# ecg_prototype_1.net
KiCad netlist of a schematic drawn in EAGLE
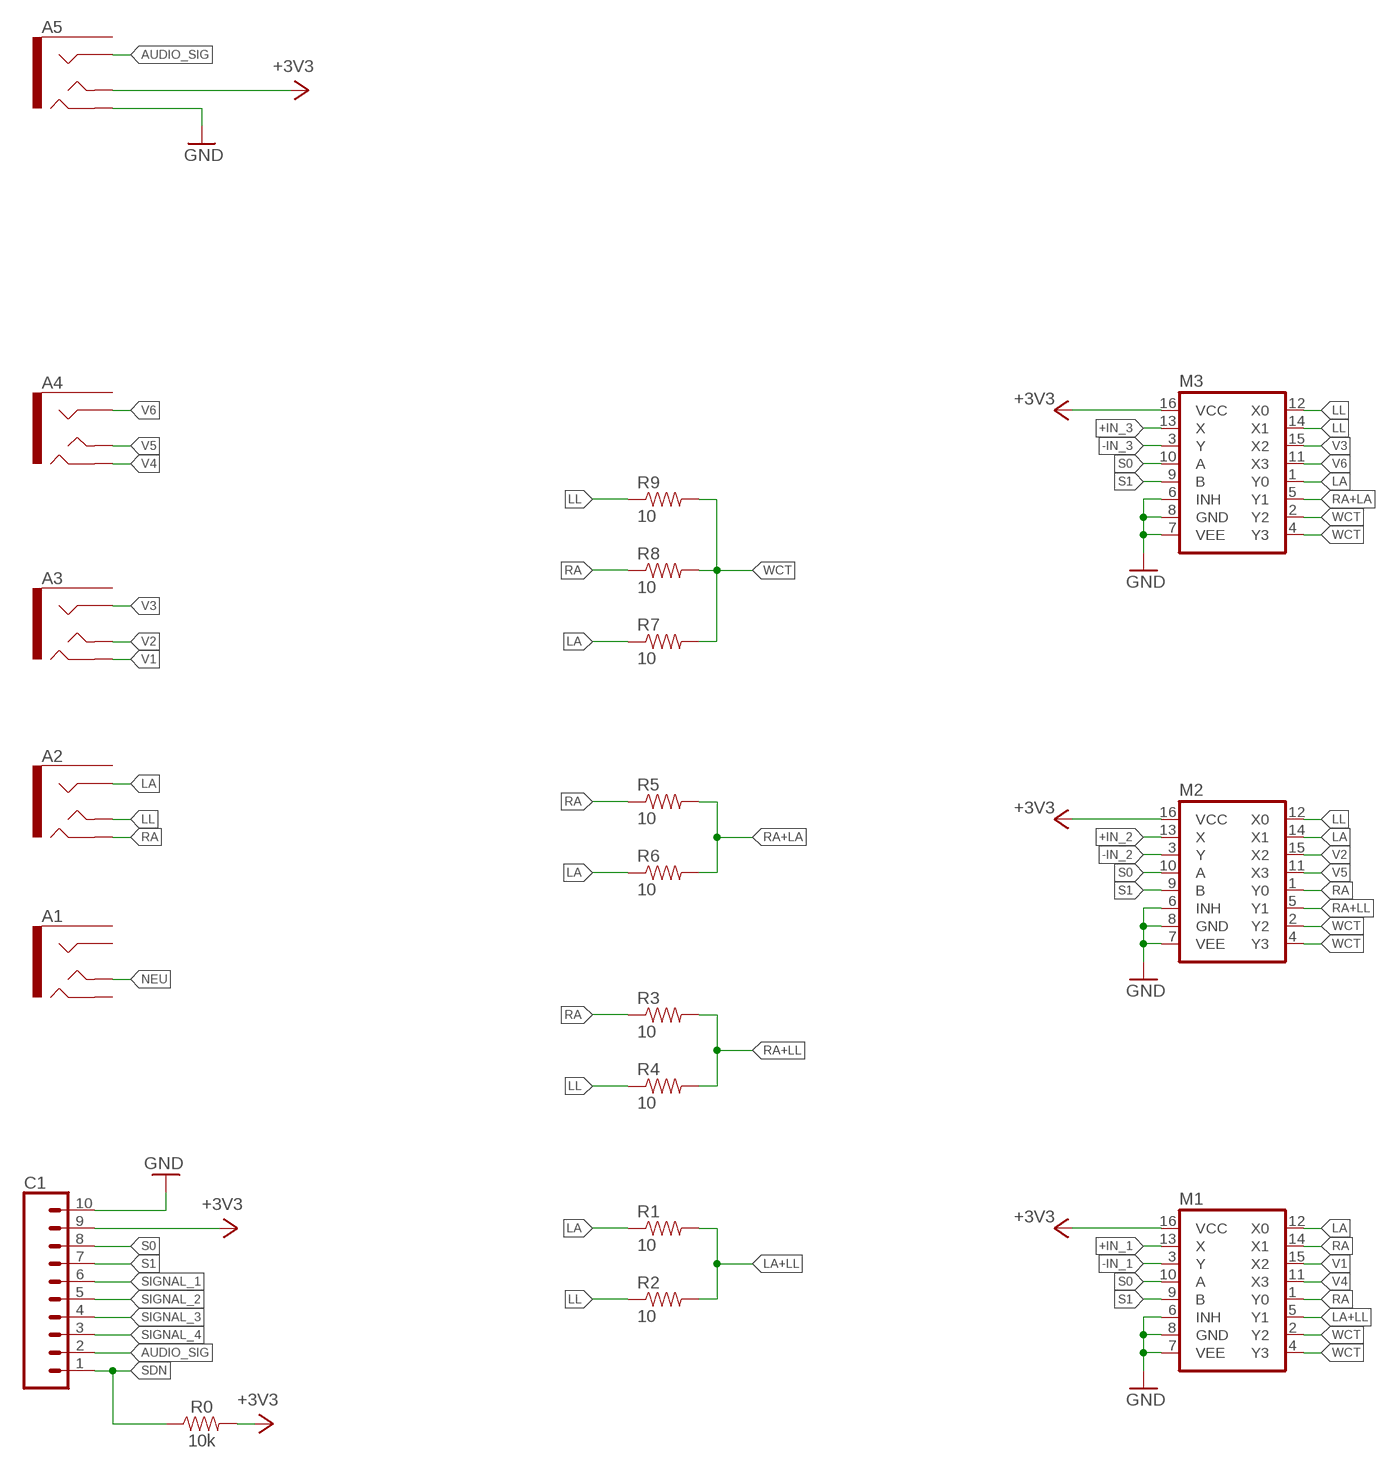
[diagram p0: schematic, sheet 1, part 1 of 2]
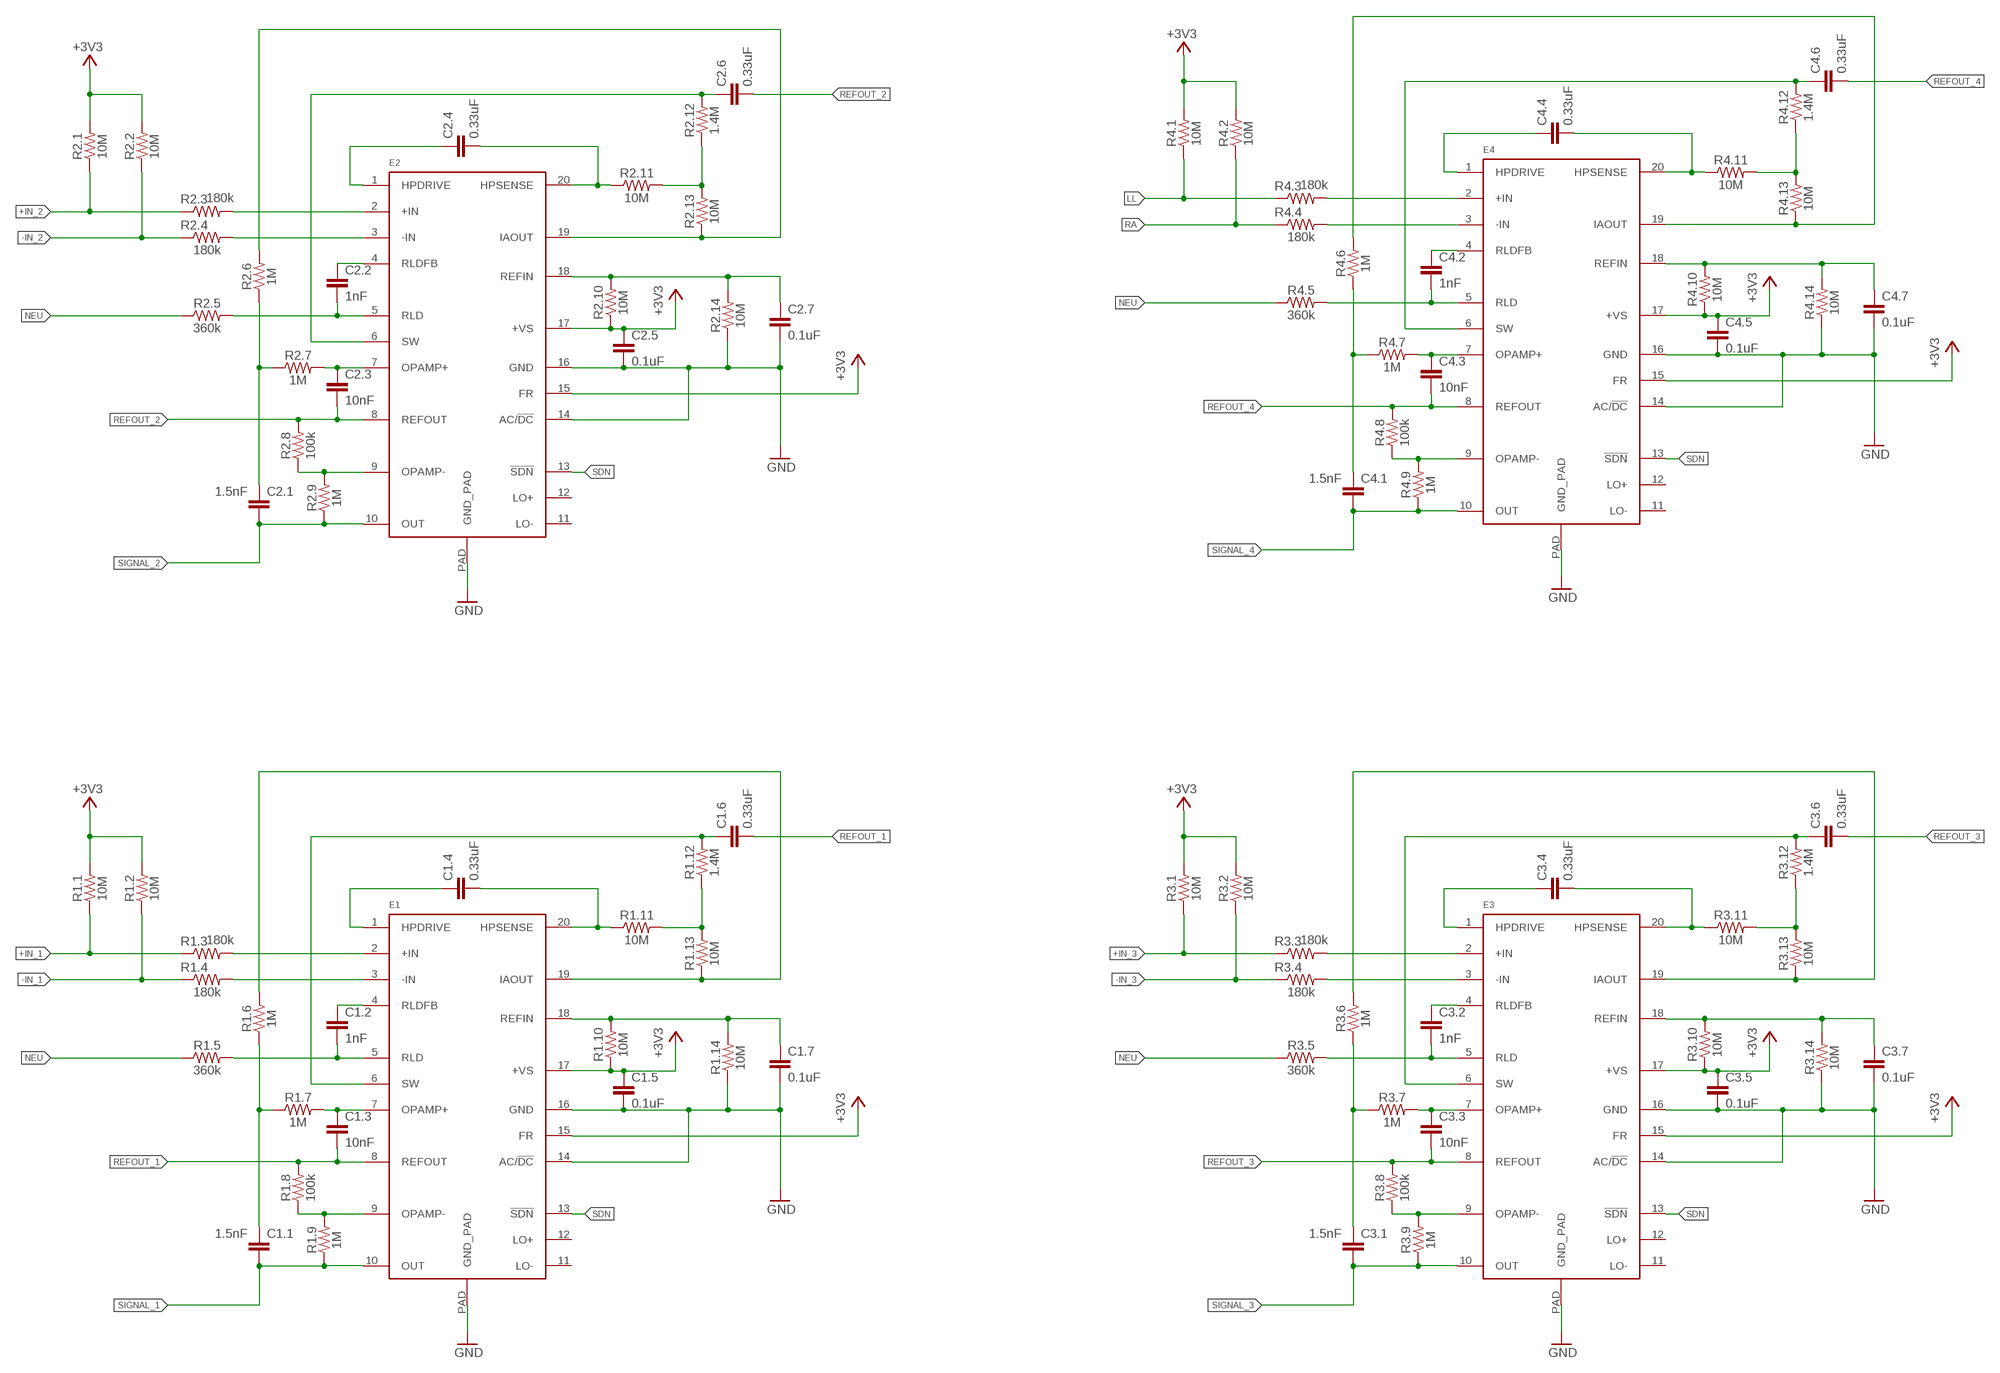
[diagram p1: schematic, sheet 1, part 2 of 2]

(export (version "E")
  (design (tool "Eeschema 10.0.6"))
  (components
    (comp (ref "A1")
      (value "AUDIO_JACK_TRRSSMD_RA")
      (footprint "eagle-import:AUDIO_JACK_3.5MM_TRRS_SMD_RA")
      (libsource (lib "eagle-import") (part "AUDIO_JACK_TRRSSMD_RA"))
    )
    (comp (ref "A2")
      (value "AUDIO_JACK_TRRSSMD_RA")
      (footprint "eagle-import:AUDIO_JACK_3.5MM_TRRS_SMD_RA")
      (libsource (lib "eagle-import") (part "AUDIO_JACK_TRRSSMD_RA"))
    )
    (comp (ref "A3")
      (value "AUDIO_JACK_TRRSSMD_RA")
      (footprint "eagle-import:AUDIO_JACK_3.5MM_TRRS_SMD_RA")
      (libsource (lib "eagle-import") (part "AUDIO_JACK_TRRSSMD_RA"))
    )
    (comp (ref "A4")
      (value "AUDIO_JACK_TRRSSMD_RA")
      (footprint "eagle-import:AUDIO_JACK_3.5MM_TRRS_SMD_RA")
      (libsource (lib "eagle-import") (part "AUDIO_JACK_TRRSSMD_RA"))
    )
    (comp (ref "A5")
      (value "AUDIO_JACK_TRRSSMD_RA")
      (footprint "eagle-import:AUDIO_JACK_3.5MM_TRRS_SMD_RA")
      (libsource (lib "eagle-import") (part "AUDIO_JACK_TRRSSMD_RA"))
    )
    (comp (ref "C1")
      (value "CONN_10\"")
      (footprint "eagle-import:1X10")
      (libsource (lib "eagle-import") (part "CONN_10{dblquote}"))
    )
    (comp (ref "C1.1")
      (value "1.5nF")
      (footprint "eagle-import:0603-CAP")
      (libsource (lib "eagle-import") (part "CAP0603-CAP"))
    )
    (comp (ref "C1.2")
      (value "1nF")
      (footprint "eagle-import:0603-CAP")
      (libsource (lib "eagle-import") (part "CAP0603-CAP"))
    )
    (comp (ref "C1.3")
      (value "10nF")
      (footprint "eagle-import:0603-CAP")
      (libsource (lib "eagle-import") (part "CAP0603-CAP"))
    )
    (comp (ref "C1.4")
      (value "0.33uF")
      (footprint "eagle-import:0805")
      (libsource (lib "eagle-import") (part "CAP0805"))
    )
    (comp (ref "C1.5")
      (value "0.1uF")
      (footprint "eagle-import:0603-CAP")
      (libsource (lib "eagle-import") (part "CAP0603-CAP"))
    )
    (comp (ref "C1.6")
      (value "0.33uF")
      (footprint "eagle-import:0805")
      (libsource (lib "eagle-import") (part "CAP0805"))
    )
    (comp (ref "C1.7")
      (value "0.1uF")
      (footprint "eagle-import:0603-CAP")
      (libsource (lib "eagle-import") (part "CAP0603-CAP"))
    )
    (comp (ref "C2.1")
      (value "1.5nF")
      (footprint "eagle-import:0603-CAP")
      (libsource (lib "eagle-import") (part "CAP0603-CAP"))
    )
    (comp (ref "C2.2")
      (value "1nF")
      (footprint "eagle-import:0603-CAP")
      (libsource (lib "eagle-import") (part "CAP0603-CAP"))
    )
    (comp (ref "C2.3")
      (value "10nF")
      (footprint "eagle-import:0603-CAP")
      (libsource (lib "eagle-import") (part "CAP0603-CAP"))
    )
    (comp (ref "C2.4")
      (value "0.33uF")
      (footprint "eagle-import:0805")
      (libsource (lib "eagle-import") (part "CAP0805"))
    )
    (comp (ref "C2.5")
      (value "0.1uF")
      (footprint "eagle-import:0603-CAP")
      (libsource (lib "eagle-import") (part "CAP0603-CAP"))
    )
    (comp (ref "C2.6")
      (value "0.33uF")
      (footprint "eagle-import:0805")
      (libsource (lib "eagle-import") (part "CAP0805"))
    )
    (comp (ref "C2.7")
      (value "0.1uF")
      (footprint "eagle-import:0603-CAP")
      (libsource (lib "eagle-import") (part "CAP0603-CAP"))
    )
    (comp (ref "C3.1")
      (value "1.5nF")
      (footprint "eagle-import:0603-CAP")
      (libsource (lib "eagle-import") (part "CAP0603-CAP"))
    )
    (comp (ref "C3.2")
      (value "1nF")
      (footprint "eagle-import:0603-CAP")
      (libsource (lib "eagle-import") (part "CAP0603-CAP"))
    )
    (comp (ref "C3.3")
      (value "10nF")
      (footprint "eagle-import:0603-CAP")
      (libsource (lib "eagle-import") (part "CAP0603-CAP"))
    )
    (comp (ref "C3.4")
      (value "0.33uF")
      (footprint "eagle-import:0805")
      (libsource (lib "eagle-import") (part "CAP0805"))
    )
    (comp (ref "C3.5")
      (value "0.1uF")
      (footprint "eagle-import:0603-CAP")
      (libsource (lib "eagle-import") (part "CAP0603-CAP"))
    )
    (comp (ref "C3.6")
      (value "0.33uF")
      (footprint "eagle-import:0805")
      (libsource (lib "eagle-import") (part "CAP0805"))
    )
    (comp (ref "C3.7")
      (value "0.1uF")
      (footprint "eagle-import:0603-CAP")
      (libsource (lib "eagle-import") (part "CAP0603-CAP"))
    )
    (comp (ref "C4.1")
      (value "1.5nF")
      (footprint "eagle-import:0603-CAP")
      (libsource (lib "eagle-import") (part "CAP0603-CAP"))
    )
    (comp (ref "C4.2")
      (value "1nF")
      (footprint "eagle-import:0603-CAP")
      (libsource (lib "eagle-import") (part "CAP0603-CAP"))
    )
    (comp (ref "C4.3")
      (value "10nF")
      (footprint "eagle-import:0603-CAP")
      (libsource (lib "eagle-import") (part "CAP0603-CAP"))
    )
    (comp (ref "C4.4")
      (value "0.33uF")
      (footprint "eagle-import:0805")
      (libsource (lib "eagle-import") (part "CAP0805"))
    )
    (comp (ref "C4.5")
      (value "0.1uF")
      (footprint "eagle-import:0603-CAP")
      (libsource (lib "eagle-import") (part "CAP0603-CAP"))
    )
    (comp (ref "C4.6")
      (value "0.33uF")
      (footprint "eagle-import:0805")
      (libsource (lib "eagle-import") (part "CAP0805"))
    )
    (comp (ref "C4.7")
      (value "0.1uF")
      (footprint "eagle-import:0603-CAP")
      (libsource (lib "eagle-import") (part "CAP0603-CAP"))
    )
    (comp (ref "E1")
      (value "AD8232ACPZ-R7")
      (footprint "eagle-import:LFCSP_20")
      (libsource (lib "eagle-import") (part "AD8232"))
    )
    (comp (ref "E2")
      (value "AD8232ACPZ-R7")
      (footprint "eagle-import:LFCSP_20")
      (libsource (lib "eagle-import") (part "AD8232"))
    )
    (comp (ref "E3")
      (value "AD8232ACPZ-R7")
      (footprint "eagle-import:LFCSP_20")
      (libsource (lib "eagle-import") (part "AD8232"))
    )
    (comp (ref "E4")
      (value "AD8232ACPZ-R7")
      (footprint "eagle-import:LFCSP_20")
      (libsource (lib "eagle-import") (part "AD8232"))
    )
    (comp (ref "M1")
      (value "74HC4052D")
      (footprint "eagle-import:SO16")
      (libsource (lib "eagle-import") (part "744052DHC"))
    )
    (comp (ref "M2")
      (value "74HC4052D")
      (footprint "eagle-import:SO16")
      (libsource (lib "eagle-import") (part "744052DHC"))
    )
    (comp (ref "M3")
      (value "74HC4052D")
      (footprint "eagle-import:SO16")
      (libsource (lib "eagle-import") (part "744052DHC"))
    )
    (comp (ref "R0")
      (value "10k")
      (footprint "eagle-import:0603")
      (libsource (lib "eagle-import") (part "10KOHM-0603-1/10W-1%"))
    )
    (comp (ref "R1")
      (value "10")
      (footprint "eagle-import:0402-RES")
      (libsource (lib "eagle-import") (part "RESISTOR0402-RES"))
    )
    (comp (ref "R1.1")
      (value "10M")
      (footprint "eagle-import:0603")
      (libsource (lib "eagle-import") (part "RESISTOR0603"))
    )
    (comp (ref "R1.2")
      (value "10M")
      (footprint "eagle-import:0603")
      (libsource (lib "eagle-import") (part "RESISTOR0603"))
    )
    (comp (ref "R1.3")
      (value "180k")
      (footprint "eagle-import:0603")
      (libsource (lib "eagle-import") (part "RESISTOR0603"))
    )
    (comp (ref "R1.4")
      (value "180k")
      (footprint "eagle-import:0603")
      (libsource (lib "eagle-import") (part "RESISTOR0603"))
    )
    (comp (ref "R1.5")
      (value "360k")
      (footprint "eagle-import:0603")
      (libsource (lib "eagle-import") (part "RESISTOR0603"))
    )
    (comp (ref "R1.6")
      (value "1M")
      (footprint "eagle-import:0603")
      (libsource (lib "eagle-import") (part "RESISTOR0603"))
    )
    (comp (ref "R1.7")
      (value "1M")
      (footprint "eagle-import:0603")
      (libsource (lib "eagle-import") (part "RESISTOR0603"))
    )
    (comp (ref "R1.8")
      (value "100k")
      (footprint "eagle-import:0603")
      (libsource (lib "eagle-import") (part "RESISTOR0603"))
    )
    (comp (ref "R1.9")
      (value "1M")
      (footprint "eagle-import:0603")
      (libsource (lib "eagle-import") (part "RESISTOR0603"))
    )
    (comp (ref "R1.10")
      (value "10M")
      (footprint "eagle-import:0603")
      (libsource (lib "eagle-import") (part "RESISTOR0603"))
    )
    (comp (ref "R1.11")
      (value "10M")
      (footprint "eagle-import:0603")
      (libsource (lib "eagle-import") (part "RESISTOR0603"))
    )
    (comp (ref "R1.12")
      (value "1.4M")
      (footprint "eagle-import:0603")
      (libsource (lib "eagle-import") (part "RESISTOR0603"))
    )
    (comp (ref "R1.13")
      (value "10M")
      (footprint "eagle-import:0603")
      (libsource (lib "eagle-import") (part "RESISTOR0603"))
    )
    (comp (ref "R1.14")
      (value "10M")
      (footprint "eagle-import:0603")
      (libsource (lib "eagle-import") (part "RESISTOR0603"))
    )
    (comp (ref "R2")
      (value "10")
      (footprint "eagle-import:0402-RES")
      (libsource (lib "eagle-import") (part "RESISTOR0402-RES"))
    )
    (comp (ref "R2.1")
      (value "10M")
      (footprint "eagle-import:0603")
      (libsource (lib "eagle-import") (part "RESISTOR0603"))
    )
    (comp (ref "R2.2")
      (value "10M")
      (footprint "eagle-import:0603")
      (libsource (lib "eagle-import") (part "RESISTOR0603"))
    )
    (comp (ref "R2.3")
      (value "180k")
      (footprint "eagle-import:0603")
      (libsource (lib "eagle-import") (part "RESISTOR0603"))
    )
    (comp (ref "R2.4")
      (value "180k")
      (footprint "eagle-import:0603")
      (libsource (lib "eagle-import") (part "RESISTOR0603"))
    )
    (comp (ref "R2.5")
      (value "360k")
      (footprint "eagle-import:0603")
      (libsource (lib "eagle-import") (part "RESISTOR0603"))
    )
    (comp (ref "R2.6")
      (value "1M")
      (footprint "eagle-import:0603")
      (libsource (lib "eagle-import") (part "RESISTOR0603"))
    )
    (comp (ref "R2.7")
      (value "1M")
      (footprint "eagle-import:0603")
      (libsource (lib "eagle-import") (part "RESISTOR0603"))
    )
    (comp (ref "R2.8")
      (value "100k")
      (footprint "eagle-import:0603")
      (libsource (lib "eagle-import") (part "RESISTOR0603"))
    )
    (comp (ref "R2.9")
      (value "1M")
      (footprint "eagle-import:0603")
      (libsource (lib "eagle-import") (part "RESISTOR0603"))
    )
    (comp (ref "R2.10")
      (value "10M")
      (footprint "eagle-import:0603")
      (libsource (lib "eagle-import") (part "RESISTOR0603"))
    )
    (comp (ref "R2.11")
      (value "10M")
      (footprint "eagle-import:0603")
      (libsource (lib "eagle-import") (part "RESISTOR0603"))
    )
    (comp (ref "R2.12")
      (value "1.4M")
      (footprint "eagle-import:0603")
      (libsource (lib "eagle-import") (part "RESISTOR0603"))
    )
    (comp (ref "R2.13")
      (value "10M")
      (footprint "eagle-import:0603")
      (libsource (lib "eagle-import") (part "RESISTOR0603"))
    )
    (comp (ref "R2.14")
      (value "10M")
      (footprint "eagle-import:0603")
      (libsource (lib "eagle-import") (part "RESISTOR0603"))
    )
    (comp (ref "R3")
      (value "10")
      (footprint "eagle-import:0402-RES")
      (libsource (lib "eagle-import") (part "RESISTOR0402-RES"))
    )
    (comp (ref "R3.1")
      (value "10M")
      (footprint "eagle-import:0603")
      (libsource (lib "eagle-import") (part "RESISTOR0603"))
    )
    (comp (ref "R3.2")
      (value "10M")
      (footprint "eagle-import:0603")
      (libsource (lib "eagle-import") (part "RESISTOR0603"))
    )
    (comp (ref "R3.3")
      (value "180k")
      (footprint "eagle-import:0603")
      (libsource (lib "eagle-import") (part "RESISTOR0603"))
    )
    (comp (ref "R3.4")
      (value "180k")
      (footprint "eagle-import:0603")
      (libsource (lib "eagle-import") (part "RESISTOR0603"))
    )
    (comp (ref "R3.5")
      (value "360k")
      (footprint "eagle-import:0603")
      (libsource (lib "eagle-import") (part "RESISTOR0603"))
    )
    (comp (ref "R3.6")
      (value "1M")
      (footprint "eagle-import:0603")
      (libsource (lib "eagle-import") (part "RESISTOR0603"))
    )
    (comp (ref "R3.7")
      (value "1M")
      (footprint "eagle-import:0603")
      (libsource (lib "eagle-import") (part "RESISTOR0603"))
    )
    (comp (ref "R3.8")
      (value "100k")
      (footprint "eagle-import:0603")
      (libsource (lib "eagle-import") (part "RESISTOR0603"))
    )
    (comp (ref "R3.9")
      (value "1M")
      (footprint "eagle-import:0603")
      (libsource (lib "eagle-import") (part "RESISTOR0603"))
    )
    (comp (ref "R3.10")
      (value "10M")
      (footprint "eagle-import:0603")
      (libsource (lib "eagle-import") (part "RESISTOR0603"))
    )
    (comp (ref "R3.11")
      (value "10M")
      (footprint "eagle-import:0603")
      (libsource (lib "eagle-import") (part "RESISTOR0603"))
    )
    (comp (ref "R3.12")
      (value "1.4M")
      (footprint "eagle-import:0603")
      (libsource (lib "eagle-import") (part "RESISTOR0603"))
    )
    (comp (ref "R3.13")
      (value "10M")
      (footprint "eagle-import:0603")
      (libsource (lib "eagle-import") (part "RESISTOR0603"))
    )
    (comp (ref "R3.14")
      (value "10M")
      (footprint "eagle-import:0603")
      (libsource (lib "eagle-import") (part "RESISTOR0603"))
    )
    (comp (ref "R4")
      (value "10")
      (footprint "eagle-import:0402-RES")
      (libsource (lib "eagle-import") (part "RESISTOR0402-RES"))
    )
    (comp (ref "R4.1")
      (value "10M")
      (footprint "eagle-import:0603")
      (libsource (lib "eagle-import") (part "RESISTOR0603"))
    )
    (comp (ref "R4.2")
      (value "10M")
      (footprint "eagle-import:0603")
      (libsource (lib "eagle-import") (part "RESISTOR0603"))
    )
    (comp (ref "R4.3")
      (value "180k")
      (footprint "eagle-import:0603")
      (libsource (lib "eagle-import") (part "RESISTOR0603"))
    )
    (comp (ref "R4.4")
      (value "180k")
      (footprint "eagle-import:0603")
      (libsource (lib "eagle-import") (part "RESISTOR0603"))
    )
    (comp (ref "R4.5")
      (value "360k")
      (footprint "eagle-import:0603")
      (libsource (lib "eagle-import") (part "RESISTOR0603"))
    )
    (comp (ref "R4.6")
      (value "1M")
      (footprint "eagle-import:0603")
      (libsource (lib "eagle-import") (part "RESISTOR0603"))
    )
    (comp (ref "R4.7")
      (value "1M")
      (footprint "eagle-import:0603")
      (libsource (lib "eagle-import") (part "RESISTOR0603"))
    )
    (comp (ref "R4.8")
      (value "100k")
      (footprint "eagle-import:0603")
      (libsource (lib "eagle-import") (part "RESISTOR0603"))
    )
    (comp (ref "R4.9")
      (value "1M")
      (footprint "eagle-import:0603")
      (libsource (lib "eagle-import") (part "RESISTOR0603"))
    )
    (comp (ref "R4.10")
      (value "10M")
      (footprint "eagle-import:0603")
      (libsource (lib "eagle-import") (part "RESISTOR0603"))
    )
    (comp (ref "R4.11")
      (value "10M")
      (footprint "eagle-import:0603")
      (libsource (lib "eagle-import") (part "RESISTOR0603"))
    )
    (comp (ref "R4.12")
      (value "1.4M")
      (footprint "eagle-import:0603")
      (libsource (lib "eagle-import") (part "RESISTOR0603"))
    )
    (comp (ref "R4.13")
      (value "10M")
      (footprint "eagle-import:0603")
      (libsource (lib "eagle-import") (part "RESISTOR0603"))
    )
    (comp (ref "R4.14")
      (value "10M")
      (footprint "eagle-import:0603")
      (libsource (lib "eagle-import") (part "RESISTOR0603"))
    )
    (comp (ref "R5")
      (value "10")
      (footprint "eagle-import:0402-RES")
      (libsource (lib "eagle-import") (part "RESISTOR0402-RES"))
    )
    (comp (ref "R6")
      (value "10")
      (footprint "eagle-import:0402-RES")
      (libsource (lib "eagle-import") (part "RESISTOR0402-RES"))
    )
    (comp (ref "R7")
      (value "10")
      (footprint "eagle-import:0402-RES")
      (libsource (lib "eagle-import") (part "RESISTOR0402-RES"))
    )
    (comp (ref "R8")
      (value "10")
      (footprint "eagle-import:0402-RES")
      (libsource (lib "eagle-import") (part "RESISTOR0402-RES"))
    )
    (comp (ref "R9")
      (value "10")
      (footprint "eagle-import:0402-RES")
      (libsource (lib "eagle-import") (part "RESISTOR0402-RES"))
    )
  )
  (nets
    (net (code "1") (name "+3V3") (class "Default")
      (node (ref "A5") (pin "TIP") (pinfunction "TIP_TIP") (pintype "bidirectional"))
      (node (ref "C1") (pin "9") (pinfunction "9_9") (pintype "passive"))
      (node (ref "C1.5") (pin "1") (pinfunction "1_1") (pintype "passive"))
      (node (ref "C2.5") (pin "1") (pinfunction "1_1") (pintype "passive"))
      (node (ref "C3.5") (pin "1") (pinfunction "1_1") (pintype "passive"))
      (node (ref "C4.5") (pin "1") (pinfunction "1_1") (pintype "passive"))
      (node (ref "E1") (pin "15") (pinfunction "FR_15") (pintype "bidirectional"))
      (node (ref "E1") (pin "17") (pinfunction "+VS_17") (pintype "bidirectional"))
      (node (ref "E2") (pin "15") (pinfunction "FR_15") (pintype "bidirectional"))
      (node (ref "E2") (pin "17") (pinfunction "+VS_17") (pintype "bidirectional"))
      (node (ref "E3") (pin "15") (pinfunction "FR_15") (pintype "bidirectional"))
      (node (ref "E3") (pin "17") (pinfunction "+VS_17") (pintype "bidirectional"))
      (node (ref "E4") (pin "15") (pinfunction "FR_15") (pintype "bidirectional"))
      (node (ref "E4") (pin "17") (pinfunction "+VS_17") (pintype "bidirectional"))
      (node (ref "M1") (pin "16") (pinfunction "VCC_16") (pintype "power_in"))
      (node (ref "M2") (pin "16") (pinfunction "VCC_16") (pintype "power_in"))
      (node (ref "M3") (pin "16") (pinfunction "VCC_16") (pintype "power_in"))
      (node (ref "R0") (pin "2") (pinfunction "2_2") (pintype "passive"))
      (node (ref "R1.1") (pin "2") (pinfunction "2_2") (pintype "passive"))
      (node (ref "R1.10") (pin "1") (pinfunction "1_1") (pintype "passive"))
      (node (ref "R1.2") (pin "2") (pinfunction "2_2") (pintype "passive"))
      (node (ref "R2.1") (pin "2") (pinfunction "2_2") (pintype "passive"))
      (node (ref "R2.10") (pin "1") (pinfunction "1_1") (pintype "passive"))
      (node (ref "R2.2") (pin "2") (pinfunction "2_2") (pintype "passive"))
      (node (ref "R3.1") (pin "2") (pinfunction "2_2") (pintype "passive"))
      (node (ref "R3.10") (pin "1") (pinfunction "1_1") (pintype "passive"))
      (node (ref "R3.2") (pin "2") (pinfunction "2_2") (pintype "passive"))
      (node (ref "R4.1") (pin "2") (pinfunction "2_2") (pintype "passive"))
      (node (ref "R4.10") (pin "1") (pinfunction "1_1") (pintype "passive"))
      (node (ref "R4.2") (pin "2") (pinfunction "2_2") (pintype "passive"))
    )
    (net (code "2") (name "+IN_1") (class "Default")
      (node (ref "M1") (pin "13") (pinfunction "X_13") (pintype "bidirectional"))
      (node (ref "R1.1") (pin "1") (pinfunction "1_1") (pintype "passive"))
      (node (ref "R1.3") (pin "1") (pinfunction "1_1") (pintype "passive"))
    )
    (net (code "3") (name "+IN_2") (class "Default")
      (node (ref "M2") (pin "13") (pinfunction "X_13") (pintype "bidirectional"))
      (node (ref "R2.1") (pin "1") (pinfunction "1_1") (pintype "passive"))
      (node (ref "R2.3") (pin "1") (pinfunction "1_1") (pintype "passive"))
    )
    (net (code "4") (name "+IN_3") (class "Default")
      (node (ref "M3") (pin "13") (pinfunction "X_13") (pintype "bidirectional"))
      (node (ref "R3.1") (pin "1") (pinfunction "1_1") (pintype "passive"))
      (node (ref "R3.3") (pin "1") (pinfunction "1_1") (pintype "passive"))
    )
    (net (code "5") (name "-IN_1") (class "Default")
      (node (ref "M1") (pin "3") (pinfunction "Y_3") (pintype "bidirectional"))
      (node (ref "R1.2") (pin "1") (pinfunction "1_1") (pintype "passive"))
      (node (ref "R1.4") (pin "1") (pinfunction "1_1") (pintype "passive"))
    )
    (net (code "6") (name "-IN_2") (class "Default")
      (node (ref "M2") (pin "3") (pinfunction "Y_3") (pintype "bidirectional"))
      (node (ref "R2.2") (pin "1") (pinfunction "1_1") (pintype "passive"))
      (node (ref "R2.4") (pin "1") (pinfunction "1_1") (pintype "passive"))
    )
    (net (code "7") (name "-IN_3") (class "Default")
      (node (ref "M3") (pin "3") (pinfunction "Y_3") (pintype "bidirectional"))
      (node (ref "R3.2") (pin "1") (pinfunction "1_1") (pintype "passive"))
      (node (ref "R3.4") (pin "1") (pinfunction "1_1") (pintype "passive"))
    )
    (net (code "8") (name "AUDIO_SIG") (class "Default")
      (node (ref "A5") (pin "RING1") (pinfunction "RING1_RING1") (pintype "bidirectional"))
      (node (ref "C1") (pin "2") (pinfunction "2_2") (pintype "passive"))
    )
    (net (code "9") (name "GND") (class "Default")
      (node (ref "A5") (pin "RING2") (pinfunction "RING2_RING2") (pintype "bidirectional"))
      (node (ref "C1") (pin "10") (pinfunction "10_10") (pintype "passive"))
      (node (ref "C1.5") (pin "2") (pinfunction "2_2") (pintype "passive"))
      (node (ref "C1.7") (pin "2") (pinfunction "2_2") (pintype "passive"))
      (node (ref "C2.5") (pin "2") (pinfunction "2_2") (pintype "passive"))
      (node (ref "C2.7") (pin "2") (pinfunction "2_2") (pintype "passive"))
      (node (ref "C3.5") (pin "2") (pinfunction "2_2") (pintype "passive"))
      (node (ref "C3.7") (pin "2") (pinfunction "2_2") (pintype "passive"))
      (node (ref "C4.5") (pin "2") (pinfunction "2_2") (pintype "passive"))
      (node (ref "C4.7") (pin "2") (pinfunction "2_2") (pintype "passive"))
      (node (ref "E1") (pin "14") (pinfunction "AC/~{DC}_14") (pintype "bidirectional"))
      (node (ref "E1") (pin "16") (pinfunction "GND_16") (pintype "bidirectional"))
      (node (ref "E1") (pin "PAD") (pinfunction "GND_PAD_PAD") (pintype "bidirectional"))
      (node (ref "E2") (pin "14") (pinfunction "AC/~{DC}_14") (pintype "bidirectional"))
      (node (ref "E2") (pin "16") (pinfunction "GND_16") (pintype "bidirectional"))
      (node (ref "E2") (pin "PAD") (pinfunction "GND_PAD_PAD") (pintype "bidirectional"))
      (node (ref "E3") (pin "14") (pinfunction "AC/~{DC}_14") (pintype "bidirectional"))
      (node (ref "E3") (pin "16") (pinfunction "GND_16") (pintype "bidirectional"))
      (node (ref "E3") (pin "PAD") (pinfunction "GND_PAD_PAD") (pintype "bidirectional"))
      (node (ref "E4") (pin "14") (pinfunction "AC/~{DC}_14") (pintype "bidirectional"))
      (node (ref "E4") (pin "16") (pinfunction "GND_16") (pintype "bidirectional"))
      (node (ref "E4") (pin "PAD") (pinfunction "GND_PAD_PAD") (pintype "bidirectional"))
      (node (ref "M1") (pin "6") (pinfunction "INH_6") (pintype "input"))
      (node (ref "M1") (pin "7") (pinfunction "VEE_7") (pintype "power_in"))
      (node (ref "M1") (pin "8") (pinfunction "GND_8") (pintype "power_in"))
      (node (ref "M2") (pin "6") (pinfunction "INH_6") (pintype "input"))
      (node (ref "M2") (pin "7") (pinfunction "VEE_7") (pintype "power_in"))
      (node (ref "M2") (pin "8") (pinfunction "GND_8") (pintype "power_in"))
      (node (ref "M3") (pin "6") (pinfunction "INH_6") (pintype "input"))
      (node (ref "M3") (pin "7") (pinfunction "VEE_7") (pintype "power_in"))
      (node (ref "M3") (pin "8") (pinfunction "GND_8") (pintype "power_in"))
      (node (ref "R1.14") (pin "1") (pinfunction "1_1") (pintype "passive"))
      (node (ref "R2.14") (pin "1") (pinfunction "1_1") (pintype "passive"))
      (node (ref "R3.14") (pin "1") (pinfunction "1_1") (pintype "passive"))
      (node (ref "R4.14") (pin "1") (pinfunction "1_1") (pintype "passive"))
    )
    (net (code "10") (name "LA") (class "Default")
      (node (ref "A2") (pin "RING1") (pinfunction "RING1_RING1") (pintype "bidirectional"))
      (node (ref "M1") (pin "12") (pinfunction "X0_12") (pintype "bidirectional"))
      (node (ref "M2") (pin "14") (pinfunction "X1_14") (pintype "bidirectional"))
      (node (ref "M3") (pin "1") (pinfunction "Y0_1") (pintype "bidirectional"))
      (node (ref "R1") (pin "1") (pinfunction "1_1") (pintype "passive"))
      (node (ref "R6") (pin "1") (pinfunction "1_1") (pintype "passive"))
      (node (ref "R7") (pin "1") (pinfunction "1_1") (pintype "passive"))
    )
    (net (code "11") (name "LA+LL") (class "Default")
      (node (ref "M1") (pin "5") (pinfunction "Y1_5") (pintype "bidirectional"))
      (node (ref "R1") (pin "2") (pinfunction "2_2") (pintype "passive"))
      (node (ref "R2") (pin "2") (pinfunction "2_2") (pintype "passive"))
    )
    (net (code "12") (name "LL") (class "Default")
      (node (ref "A2") (pin "TIP") (pinfunction "TIP_TIP") (pintype "bidirectional"))
      (node (ref "M2") (pin "12") (pinfunction "X0_12") (pintype "bidirectional"))
      (node (ref "M3") (pin "12") (pinfunction "X0_12") (pintype "bidirectional"))
      (node (ref "M3") (pin "14") (pinfunction "X1_14") (pintype "bidirectional"))
      (node (ref "R2") (pin "1") (pinfunction "1_1") (pintype "passive"))
      (node (ref "R4") (pin "1") (pinfunction "1_1") (pintype "passive"))
      (node (ref "R4.1") (pin "1") (pinfunction "1_1") (pintype "passive"))
      (node (ref "R4.3") (pin "1") (pinfunction "1_1") (pintype "passive"))
      (node (ref "R9") (pin "1") (pinfunction "1_1") (pintype "passive"))
    )
    (net (code "13") (name "NEU") (class "Default")
      (node (ref "A1") (pin "TIP") (pinfunction "TIP_TIP") (pintype "bidirectional"))
      (node (ref "R1.5") (pin "1") (pinfunction "1_1") (pintype "passive"))
      (node (ref "R2.5") (pin "1") (pinfunction "1_1") (pintype "passive"))
      (node (ref "R3.5") (pin "1") (pinfunction "1_1") (pintype "passive"))
      (node (ref "R4.5") (pin "1") (pinfunction "1_1") (pintype "passive"))
    )
    (net (code "14") (name "Net-(C1.1-Pad1)") (class "Default")
      (node (ref "C1.1") (pin "1") (pinfunction "1_1") (pintype "passive"))
      (node (ref "R1.6") (pin "1") (pinfunction "1_1") (pintype "passive"))
      (node (ref "R1.7") (pin "1") (pinfunction "1_1") (pintype "passive"))
    )
    (net (code "15") (name "Net-(C2.1-Pad1)") (class "Default")
      (node (ref "C2.1") (pin "1") (pinfunction "1_1") (pintype "passive"))
      (node (ref "R2.6") (pin "1") (pinfunction "1_1") (pintype "passive"))
      (node (ref "R2.7") (pin "1") (pinfunction "1_1") (pintype "passive"))
    )
    (net (code "16") (name "Net-(C3.1-Pad1)") (class "Default")
      (node (ref "C3.1") (pin "1") (pinfunction "1_1") (pintype "passive"))
      (node (ref "R3.6") (pin "1") (pinfunction "1_1") (pintype "passive"))
      (node (ref "R3.7") (pin "1") (pinfunction "1_1") (pintype "passive"))
    )
    (net (code "17") (name "Net-(C4.1-Pad1)") (class "Default")
      (node (ref "C4.1") (pin "1") (pinfunction "1_1") (pintype "passive"))
      (node (ref "R4.6") (pin "1") (pinfunction "1_1") (pintype "passive"))
      (node (ref "R4.7") (pin "1") (pinfunction "1_1") (pintype "passive"))
    )
    (net (code "18") (name "Net-(E1-+IN)") (class "Default")
      (node (ref "E1") (pin "2") (pinfunction "+IN_2") (pintype "bidirectional"))
      (node (ref "R1.3") (pin "2") (pinfunction "2_2") (pintype "passive"))
    )
    (net (code "19") (name "Net-(E1--IN)") (class "Default")
      (node (ref "E1") (pin "3") (pinfunction "-IN_3") (pintype "bidirectional"))
      (node (ref "R1.4") (pin "2") (pinfunction "2_2") (pintype "passive"))
    )
    (net (code "20") (name "Net-(E1-HPDRIVE)") (class "Default")
      (node (ref "C1.4") (pin "1") (pinfunction "1_1") (pintype "passive"))
      (node (ref "E1") (pin "1") (pinfunction "HPDRIVE_1") (pintype "bidirectional"))
    )
    (net (code "21") (name "Net-(E1-HPSENSE)") (class "Default")
      (node (ref "C1.4") (pin "2") (pinfunction "2_2") (pintype "passive"))
      (node (ref "E1") (pin "20") (pinfunction "HPSENSE_20") (pintype "bidirectional"))
      (node (ref "R1.11") (pin "1") (pinfunction "1_1") (pintype "passive"))
    )
    (net (code "22") (name "Net-(E1-IAOUT)") (class "Default")
      (node (ref "E1") (pin "19") (pinfunction "IAOUT_19") (pintype "bidirectional"))
      (node (ref "R1.13") (pin "1") (pinfunction "1_1") (pintype "passive"))
      (node (ref "R1.6") (pin "2") (pinfunction "2_2") (pintype "passive"))
    )
    (net (code "23") (name "Net-(E1-OPAMP+)") (class "Default")
      (node (ref "C1.3") (pin "1") (pinfunction "1_1") (pintype "passive"))
      (node (ref "E1") (pin "7") (pinfunction "OPAMP+_7") (pintype "bidirectional"))
      (node (ref "R1.7") (pin "2") (pinfunction "2_2") (pintype "passive"))
    )
    (net (code "24") (name "Net-(E1-OPAMP-)") (class "Default")
      (node (ref "E1") (pin "9") (pinfunction "OPAMP-_9") (pintype "bidirectional"))
      (node (ref "R1.8") (pin "1") (pinfunction "1_1") (pintype "passive"))
      (node (ref "R1.9") (pin "2") (pinfunction "2_2") (pintype "passive"))
    )
    (net (code "25") (name "Net-(E1-REFIN)") (class "Default")
      (node (ref "C1.7") (pin "1") (pinfunction "1_1") (pintype "passive"))
      (node (ref "E1") (pin "18") (pinfunction "REFIN_18") (pintype "bidirectional"))
      (node (ref "R1.10") (pin "2") (pinfunction "2_2") (pintype "passive"))
      (node (ref "R1.14") (pin "2") (pinfunction "2_2") (pintype "passive"))
    )
    (net (code "26") (name "Net-(E1-RLD)") (class "Default")
      (node (ref "C1.2") (pin "2") (pinfunction "2_2") (pintype "passive"))
      (node (ref "E1") (pin "5") (pinfunction "RLD_5") (pintype "bidirectional"))
      (node (ref "R1.5") (pin "2") (pinfunction "2_2") (pintype "passive"))
    )
    (net (code "27") (name "Net-(E1-RLDFB)") (class "Default")
      (node (ref "C1.2") (pin "1") (pinfunction "1_1") (pintype "passive"))
      (node (ref "E1") (pin "4") (pinfunction "RLDFB_4") (pintype "bidirectional"))
    )
    (net (code "28") (name "Net-(E1-SW)") (class "Default")
      (node (ref "C1.6") (pin "1") (pinfunction "1_1") (pintype "passive"))
      (node (ref "E1") (pin "6") (pinfunction "SW_6") (pintype "bidirectional"))
      (node (ref "R1.12") (pin "2") (pinfunction "2_2") (pintype "passive"))
    )
    (net (code "29") (name "Net-(E2-+IN)") (class "Default")
      (node (ref "E2") (pin "2") (pinfunction "+IN_2") (pintype "bidirectional"))
      (node (ref "R2.3") (pin "2") (pinfunction "2_2") (pintype "passive"))
    )
    (net (code "30") (name "Net-(E2--IN)") (class "Default")
      (node (ref "E2") (pin "3") (pinfunction "-IN_3") (pintype "bidirectional"))
      (node (ref "R2.4") (pin "2") (pinfunction "2_2") (pintype "passive"))
    )
    (net (code "31") (name "Net-(E2-HPDRIVE)") (class "Default")
      (node (ref "C2.4") (pin "1") (pinfunction "1_1") (pintype "passive"))
      (node (ref "E2") (pin "1") (pinfunction "HPDRIVE_1") (pintype "bidirectional"))
    )
    (net (code "32") (name "Net-(E2-HPSENSE)") (class "Default")
      (node (ref "C2.4") (pin "2") (pinfunction "2_2") (pintype "passive"))
      (node (ref "E2") (pin "20") (pinfunction "HPSENSE_20") (pintype "bidirectional"))
      (node (ref "R2.11") (pin "1") (pinfunction "1_1") (pintype "passive"))
    )
    (net (code "33") (name "Net-(E2-IAOUT)") (class "Default")
      (node (ref "E2") (pin "19") (pinfunction "IAOUT_19") (pintype "bidirectional"))
      (node (ref "R2.13") (pin "1") (pinfunction "1_1") (pintype "passive"))
      (node (ref "R2.6") (pin "2") (pinfunction "2_2") (pintype "passive"))
    )
    (net (code "34") (name "Net-(E2-OPAMP+)") (class "Default")
      (node (ref "C2.3") (pin "1") (pinfunction "1_1") (pintype "passive"))
      (node (ref "E2") (pin "7") (pinfunction "OPAMP+_7") (pintype "bidirectional"))
      (node (ref "R2.7") (pin "2") (pinfunction "2_2") (pintype "passive"))
    )
    (net (code "35") (name "Net-(E2-OPAMP-)") (class "Default")
      (node (ref "E2") (pin "9") (pinfunction "OPAMP-_9") (pintype "bidirectional"))
      (node (ref "R2.8") (pin "1") (pinfunction "1_1") (pintype "passive"))
      (node (ref "R2.9") (pin "2") (pinfunction "2_2") (pintype "passive"))
    )
    (net (code "36") (name "Net-(E2-REFIN)") (class "Default")
      (node (ref "C2.7") (pin "1") (pinfunction "1_1") (pintype "passive"))
      (node (ref "E2") (pin "18") (pinfunction "REFIN_18") (pintype "bidirectional"))
      (node (ref "R2.10") (pin "2") (pinfunction "2_2") (pintype "passive"))
      (node (ref "R2.14") (pin "2") (pinfunction "2_2") (pintype "passive"))
    )
    (net (code "37") (name "Net-(E2-RLD)") (class "Default")
      (node (ref "C2.2") (pin "2") (pinfunction "2_2") (pintype "passive"))
      (node (ref "E2") (pin "5") (pinfunction "RLD_5") (pintype "bidirectional"))
      (node (ref "R2.5") (pin "2") (pinfunction "2_2") (pintype "passive"))
    )
    (net (code "38") (name "Net-(E2-RLDFB)") (class "Default")
      (node (ref "C2.2") (pin "1") (pinfunction "1_1") (pintype "passive"))
      (node (ref "E2") (pin "4") (pinfunction "RLDFB_4") (pintype "bidirectional"))
    )
    (net (code "39") (name "Net-(E2-SW)") (class "Default")
      (node (ref "C2.6") (pin "1") (pinfunction "1_1") (pintype "passive"))
      (node (ref "E2") (pin "6") (pinfunction "SW_6") (pintype "bidirectional"))
      (node (ref "R2.12") (pin "2") (pinfunction "2_2") (pintype "passive"))
    )
    (net (code "40") (name "Net-(E3-+IN)") (class "Default")
      (node (ref "E3") (pin "2") (pinfunction "+IN_2") (pintype "bidirectional"))
      (node (ref "R3.3") (pin "2") (pinfunction "2_2") (pintype "passive"))
    )
    (net (code "41") (name "Net-(E3--IN)") (class "Default")
      (node (ref "E3") (pin "3") (pinfunction "-IN_3") (pintype "bidirectional"))
      (node (ref "R3.4") (pin "2") (pinfunction "2_2") (pintype "passive"))
    )
    (net (code "42") (name "Net-(E3-HPDRIVE)") (class "Default")
      (node (ref "C3.4") (pin "1") (pinfunction "1_1") (pintype "passive"))
      (node (ref "E3") (pin "1") (pinfunction "HPDRIVE_1") (pintype "bidirectional"))
    )
    (net (code "43") (name "Net-(E3-HPSENSE)") (class "Default")
      (node (ref "C3.4") (pin "2") (pinfunction "2_2") (pintype "passive"))
      (node (ref "E3") (pin "20") (pinfunction "HPSENSE_20") (pintype "bidirectional"))
      (node (ref "R3.11") (pin "1") (pinfunction "1_1") (pintype "passive"))
    )
    (net (code "44") (name "Net-(E3-IAOUT)") (class "Default")
      (node (ref "E3") (pin "19") (pinfunction "IAOUT_19") (pintype "bidirectional"))
      (node (ref "R3.13") (pin "1") (pinfunction "1_1") (pintype "passive"))
      (node (ref "R3.6") (pin "2") (pinfunction "2_2") (pintype "passive"))
    )
    (net (code "45") (name "Net-(E3-OPAMP+)") (class "Default")
      (node (ref "C3.3") (pin "1") (pinfunction "1_1") (pintype "passive"))
      (node (ref "E3") (pin "7") (pinfunction "OPAMP+_7") (pintype "bidirectional"))
      (node (ref "R3.7") (pin "2") (pinfunction "2_2") (pintype "passive"))
    )
    (net (code "46") (name "Net-(E3-OPAMP-)") (class "Default")
      (node (ref "E3") (pin "9") (pinfunction "OPAMP-_9") (pintype "bidirectional"))
      (node (ref "R3.8") (pin "1") (pinfunction "1_1") (pintype "passive"))
      (node (ref "R3.9") (pin "2") (pinfunction "2_2") (pintype "passive"))
    )
    (net (code "47") (name "Net-(E3-REFIN)") (class "Default")
      (node (ref "C3.7") (pin "1") (pinfunction "1_1") (pintype "passive"))
      (node (ref "E3") (pin "18") (pinfunction "REFIN_18") (pintype "bidirectional"))
      (node (ref "R3.10") (pin "2") (pinfunction "2_2") (pintype "passive"))
      (node (ref "R3.14") (pin "2") (pinfunction "2_2") (pintype "passive"))
    )
    (net (code "48") (name "Net-(E3-RLD)") (class "Default")
      (node (ref "C3.2") (pin "2") (pinfunction "2_2") (pintype "passive"))
      (node (ref "E3") (pin "5") (pinfunction "RLD_5") (pintype "bidirectional"))
      (node (ref "R3.5") (pin "2") (pinfunction "2_2") (pintype "passive"))
    )
    (net (code "49") (name "Net-(E3-RLDFB)") (class "Default")
      (node (ref "C3.2") (pin "1") (pinfunction "1_1") (pintype "passive"))
      (node (ref "E3") (pin "4") (pinfunction "RLDFB_4") (pintype "bidirectional"))
    )
    (net (code "50") (name "Net-(E3-SW)") (class "Default")
      (node (ref "C3.6") (pin "1") (pinfunction "1_1") (pintype "passive"))
      (node (ref "E3") (pin "6") (pinfunction "SW_6") (pintype "bidirectional"))
      (node (ref "R3.12") (pin "2") (pinfunction "2_2") (pintype "passive"))
    )
    (net (code "51") (name "Net-(E4-+IN)") (class "Default")
      (node (ref "E4") (pin "2") (pinfunction "+IN_2") (pintype "bidirectional"))
      (node (ref "R4.3") (pin "2") (pinfunction "2_2") (pintype "passive"))
    )
    (net (code "52") (name "Net-(E4--IN)") (class "Default")
      (node (ref "E4") (pin "3") (pinfunction "-IN_3") (pintype "bidirectional"))
      (node (ref "R4.4") (pin "2") (pinfunction "2_2") (pintype "passive"))
    )
    (net (code "53") (name "Net-(E4-HPDRIVE)") (class "Default")
      (node (ref "C4.4") (pin "1") (pinfunction "1_1") (pintype "passive"))
      (node (ref "E4") (pin "1") (pinfunction "HPDRIVE_1") (pintype "bidirectional"))
    )
    (net (code "54") (name "Net-(E4-HPSENSE)") (class "Default")
      (node (ref "C4.4") (pin "2") (pinfunction "2_2") (pintype "passive"))
      (node (ref "E4") (pin "20") (pinfunction "HPSENSE_20") (pintype "bidirectional"))
      (node (ref "R4.11") (pin "1") (pinfunction "1_1") (pintype "passive"))
    )
    (net (code "55") (name "Net-(E4-IAOUT)") (class "Default")
      (node (ref "E4") (pin "19") (pinfunction "IAOUT_19") (pintype "bidirectional"))
      (node (ref "R4.13") (pin "1") (pinfunction "1_1") (pintype "passive"))
      (node (ref "R4.6") (pin "2") (pinfunction "2_2") (pintype "passive"))
    )
    (net (code "56") (name "Net-(E4-OPAMP+)") (class "Default")
      (node (ref "C4.3") (pin "1") (pinfunction "1_1") (pintype "passive"))
      (node (ref "E4") (pin "7") (pinfunction "OPAMP+_7") (pintype "bidirectional"))
      (node (ref "R4.7") (pin "2") (pinfunction "2_2") (pintype "passive"))
    )
    (net (code "57") (name "Net-(E4-OPAMP-)") (class "Default")
      (node (ref "E4") (pin "9") (pinfunction "OPAMP-_9") (pintype "bidirectional"))
      (node (ref "R4.8") (pin "1") (pinfunction "1_1") (pintype "passive"))
      (node (ref "R4.9") (pin "2") (pinfunction "2_2") (pintype "passive"))
    )
    (net (code "58") (name "Net-(E4-REFIN)") (class "Default")
      (node (ref "C4.7") (pin "1") (pinfunction "1_1") (pintype "passive"))
      (node (ref "E4") (pin "18") (pinfunction "REFIN_18") (pintype "bidirectional"))
      (node (ref "R4.10") (pin "2") (pinfunction "2_2") (pintype "passive"))
      (node (ref "R4.14") (pin "2") (pinfunction "2_2") (pintype "passive"))
    )
    (net (code "59") (name "Net-(E4-RLD)") (class "Default")
      (node (ref "C4.2") (pin "2") (pinfunction "2_2") (pintype "passive"))
      (node (ref "E4") (pin "5") (pinfunction "RLD_5") (pintype "bidirectional"))
      (node (ref "R4.5") (pin "2") (pinfunction "2_2") (pintype "passive"))
    )
    (net (code "60") (name "Net-(E4-RLDFB)") (class "Default")
      (node (ref "C4.2") (pin "1") (pinfunction "1_1") (pintype "passive"))
      (node (ref "E4") (pin "4") (pinfunction "RLDFB_4") (pintype "bidirectional"))
    )
    (net (code "61") (name "Net-(E4-SW)") (class "Default")
      (node (ref "C4.6") (pin "1") (pinfunction "1_1") (pintype "passive"))
      (node (ref "E4") (pin "6") (pinfunction "SW_6") (pintype "bidirectional"))
      (node (ref "R4.12") (pin "2") (pinfunction "2_2") (pintype "passive"))
    )
    (net (code "62") (name "Net-(R1.11-Pad2)") (class "Default")
      (node (ref "R1.11") (pin "2") (pinfunction "2_2") (pintype "passive"))
      (node (ref "R1.12") (pin "1") (pinfunction "1_1") (pintype "passive"))
      (node (ref "R1.13") (pin "2") (pinfunction "2_2") (pintype "passive"))
    )
    (net (code "63") (name "Net-(R2.11-Pad2)") (class "Default")
      (node (ref "R2.11") (pin "2") (pinfunction "2_2") (pintype "passive"))
      (node (ref "R2.12") (pin "1") (pinfunction "1_1") (pintype "passive"))
      (node (ref "R2.13") (pin "2") (pinfunction "2_2") (pintype "passive"))
    )
    (net (code "64") (name "Net-(R3.11-Pad2)") (class "Default")
      (node (ref "R3.11") (pin "2") (pinfunction "2_2") (pintype "passive"))
      (node (ref "R3.12") (pin "1") (pinfunction "1_1") (pintype "passive"))
      (node (ref "R3.13") (pin "2") (pinfunction "2_2") (pintype "passive"))
    )
    (net (code "65") (name "Net-(R4.11-Pad2)") (class "Default")
      (node (ref "R4.11") (pin "2") (pinfunction "2_2") (pintype "passive"))
      (node (ref "R4.12") (pin "1") (pinfunction "1_1") (pintype "passive"))
      (node (ref "R4.13") (pin "2") (pinfunction "2_2") (pintype "passive"))
    )
    (net (code "66") (name "RA") (class "Default")
      (node (ref "A2") (pin "RING2") (pinfunction "RING2_RING2") (pintype "bidirectional"))
      (node (ref "M1") (pin "1") (pinfunction "Y0_1") (pintype "bidirectional"))
      (node (ref "M1") (pin "14") (pinfunction "X1_14") (pintype "bidirectional"))
      (node (ref "M2") (pin "1") (pinfunction "Y0_1") (pintype "bidirectional"))
      (node (ref "R3") (pin "1") (pinfunction "1_1") (pintype "passive"))
      (node (ref "R4.2") (pin "1") (pinfunction "1_1") (pintype "passive"))
      (node (ref "R4.4") (pin "1") (pinfunction "1_1") (pintype "passive"))
      (node (ref "R5") (pin "1") (pinfunction "1_1") (pintype "passive"))
      (node (ref "R8") (pin "1") (pinfunction "1_1") (pintype "passive"))
    )
    (net (code "67") (name "RA+LA") (class "Default")
      (node (ref "M3") (pin "5") (pinfunction "Y1_5") (pintype "bidirectional"))
      (node (ref "R5") (pin "2") (pinfunction "2_2") (pintype "passive"))
      (node (ref "R6") (pin "2") (pinfunction "2_2") (pintype "passive"))
    )
    (net (code "68") (name "RA+LL") (class "Default")
      (node (ref "M2") (pin "5") (pinfunction "Y1_5") (pintype "bidirectional"))
      (node (ref "R3") (pin "2") (pinfunction "2_2") (pintype "passive"))
      (node (ref "R4") (pin "2") (pinfunction "2_2") (pintype "passive"))
    )
    (net (code "69") (name "REFOUT_1") (class "Default")
      (node (ref "C1.3") (pin "2") (pinfunction "2_2") (pintype "passive"))
      (node (ref "C1.6") (pin "2") (pinfunction "2_2") (pintype "passive"))
      (node (ref "E1") (pin "8") (pinfunction "REFOUT_8") (pintype "bidirectional"))
      (node (ref "R1.8") (pin "2") (pinfunction "2_2") (pintype "passive"))
    )
    (net (code "70") (name "REFOUT_2") (class "Default")
      (node (ref "C2.3") (pin "2") (pinfunction "2_2") (pintype "passive"))
      (node (ref "C2.6") (pin "2") (pinfunction "2_2") (pintype "passive"))
      (node (ref "E2") (pin "8") (pinfunction "REFOUT_8") (pintype "bidirectional"))
      (node (ref "R2.8") (pin "2") (pinfunction "2_2") (pintype "passive"))
    )
    (net (code "71") (name "REFOUT_3") (class "Default")
      (node (ref "C3.3") (pin "2") (pinfunction "2_2") (pintype "passive"))
      (node (ref "C3.6") (pin "2") (pinfunction "2_2") (pintype "passive"))
      (node (ref "E3") (pin "8") (pinfunction "REFOUT_8") (pintype "bidirectional"))
      (node (ref "R3.8") (pin "2") (pinfunction "2_2") (pintype "passive"))
    )
    (net (code "72") (name "REFOUT_4") (class "Default")
      (node (ref "C4.3") (pin "2") (pinfunction "2_2") (pintype "passive"))
      (node (ref "C4.6") (pin "2") (pinfunction "2_2") (pintype "passive"))
      (node (ref "E4") (pin "8") (pinfunction "REFOUT_8") (pintype "bidirectional"))
      (node (ref "R4.8") (pin "2") (pinfunction "2_2") (pintype "passive"))
    )
    (net (code "73") (name "S0") (class "Default")
      (node (ref "C1") (pin "8") (pinfunction "8_8") (pintype "passive"))
      (node (ref "M1") (pin "10") (pinfunction "A_10") (pintype "input"))
      (node (ref "M2") (pin "10") (pinfunction "A_10") (pintype "input"))
      (node (ref "M3") (pin "10") (pinfunction "A_10") (pintype "input"))
    )
    (net (code "74") (name "S1") (class "Default")
      (node (ref "C1") (pin "7") (pinfunction "7_7") (pintype "passive"))
      (node (ref "M1") (pin "9") (pinfunction "B_9") (pintype "input"))
      (node (ref "M2") (pin "9") (pinfunction "B_9") (pintype "input"))
      (node (ref "M3") (pin "9") (pinfunction "B_9") (pintype "input"))
    )
    (net (code "75") (name "SDN") (class "Default")
      (node (ref "C1") (pin "1") (pinfunction "1_1") (pintype "passive"))
      (node (ref "E1") (pin "13") (pinfunction "~{SDN}_13") (pintype "bidirectional"))
      (node (ref "E2") (pin "13") (pinfunction "~{SDN}_13") (pintype "bidirectional"))
      (node (ref "E3") (pin "13") (pinfunction "~{SDN}_13") (pintype "bidirectional"))
      (node (ref "E4") (pin "13") (pinfunction "~{SDN}_13") (pintype "bidirectional"))
      (node (ref "R0") (pin "1") (pinfunction "1_1") (pintype "passive"))
    )
    (net (code "76") (name "SIGNAL_1") (class "Default")
      (node (ref "C1") (pin "6") (pinfunction "6_6") (pintype "passive"))
      (node (ref "C1.1") (pin "2") (pinfunction "2_2") (pintype "passive"))
      (node (ref "E1") (pin "10") (pinfunction "OUT_10") (pintype "bidirectional"))
      (node (ref "R1.9") (pin "1") (pinfunction "1_1") (pintype "passive"))
    )
    (net (code "77") (name "SIGNAL_2") (class "Default")
      (node (ref "C1") (pin "5") (pinfunction "5_5") (pintype "passive"))
      (node (ref "C2.1") (pin "2") (pinfunction "2_2") (pintype "passive"))
      (node (ref "E2") (pin "10") (pinfunction "OUT_10") (pintype "bidirectional"))
      (node (ref "R2.9") (pin "1") (pinfunction "1_1") (pintype "passive"))
    )
    (net (code "78") (name "SIGNAL_3") (class "Default")
      (node (ref "C1") (pin "4") (pinfunction "4_4") (pintype "passive"))
      (node (ref "C3.1") (pin "2") (pinfunction "2_2") (pintype "passive"))
      (node (ref "E3") (pin "10") (pinfunction "OUT_10") (pintype "bidirectional"))
      (node (ref "R3.9") (pin "1") (pinfunction "1_1") (pintype "passive"))
    )
    (net (code "79") (name "SIGNAL_4") (class "Default")
      (node (ref "C1") (pin "3") (pinfunction "3_3") (pintype "passive"))
      (node (ref "C4.1") (pin "2") (pinfunction "2_2") (pintype "passive"))
      (node (ref "E4") (pin "10") (pinfunction "OUT_10") (pintype "bidirectional"))
      (node (ref "R4.9") (pin "1") (pinfunction "1_1") (pintype "passive"))
    )
    (net (code "80") (name "V1") (class "Default")
      (node (ref "A3") (pin "RING2") (pinfunction "RING2_RING2") (pintype "bidirectional"))
      (node (ref "M1") (pin "15") (pinfunction "X2_15") (pintype "bidirectional"))
    )
    (net (code "81") (name "V2") (class "Default")
      (node (ref "A3") (pin "TIP") (pinfunction "TIP_TIP") (pintype "bidirectional"))
      (node (ref "M2") (pin "15") (pinfunction "X2_15") (pintype "bidirectional"))
    )
    (net (code "82") (name "V3") (class "Default")
      (node (ref "A3") (pin "RING1") (pinfunction "RING1_RING1") (pintype "bidirectional"))
      (node (ref "M3") (pin "15") (pinfunction "X2_15") (pintype "bidirectional"))
    )
    (net (code "83") (name "V4") (class "Default")
      (node (ref "A4") (pin "RING2") (pinfunction "RING2_RING2") (pintype "bidirectional"))
      (node (ref "M1") (pin "11") (pinfunction "X3_11") (pintype "bidirectional"))
    )
    (net (code "84") (name "V5") (class "Default")
      (node (ref "A4") (pin "TIP") (pinfunction "TIP_TIP") (pintype "bidirectional"))
      (node (ref "M2") (pin "11") (pinfunction "X3_11") (pintype "bidirectional"))
    )
    (net (code "85") (name "V6") (class "Default")
      (node (ref "A4") (pin "RING1") (pinfunction "RING1_RING1") (pintype "bidirectional"))
      (node (ref "M3") (pin "11") (pinfunction "X3_11") (pintype "bidirectional"))
    )
    (net (code "86") (name "WCT") (class "Default")
      (node (ref "M1") (pin "2") (pinfunction "Y2_2") (pintype "bidirectional"))
      (node (ref "M1") (pin "4") (pinfunction "Y3_4") (pintype "bidirectional"))
      (node (ref "M2") (pin "2") (pinfunction "Y2_2") (pintype "bidirectional"))
      (node (ref "M2") (pin "4") (pinfunction "Y3_4") (pintype "bidirectional"))
      (node (ref "M3") (pin "2") (pinfunction "Y2_2") (pintype "bidirectional"))
      (node (ref "M3") (pin "4") (pinfunction "Y3_4") (pintype "bidirectional"))
      (node (ref "R7") (pin "2") (pinfunction "2_2") (pintype "passive"))
      (node (ref "R8") (pin "2") (pinfunction "2_2") (pintype "passive"))
      (node (ref "R9") (pin "2") (pinfunction "2_2") (pintype "passive"))
    )
    (net (code "87") (name "unconnected-(A1-PadEARTH)") (class "Default")
      (node (ref "A1") (pin "EARTH") (pinfunction "EARTH_EARTH") (pintype "bidirectional"))
    )
    (net (code "88") (name "unconnected-(A1-PadRING1)") (class "Default")
      (node (ref "A1") (pin "RING1") (pinfunction "RING1_RING1") (pintype "bidirectional"))
    )
    (net (code "89") (name "unconnected-(A1-PadRING2)") (class "Default")
      (node (ref "A1") (pin "RING2") (pinfunction "RING2_RING2") (pintype "bidirectional"))
    )
    (net (code "90") (name "unconnected-(A2-PadEARTH)") (class "Default")
      (node (ref "A2") (pin "EARTH") (pinfunction "EARTH_EARTH") (pintype "bidirectional"))
    )
    (net (code "91") (name "unconnected-(A3-PadEARTH)") (class "Default")
      (node (ref "A3") (pin "EARTH") (pinfunction "EARTH_EARTH") (pintype "bidirectional"))
    )
    (net (code "92") (name "unconnected-(A4-PadEARTH)") (class "Default")
      (node (ref "A4") (pin "EARTH") (pinfunction "EARTH_EARTH") (pintype "bidirectional"))
    )
    (net (code "93") (name "unconnected-(A5-PadEARTH)") (class "Default")
      (node (ref "A5") (pin "EARTH") (pinfunction "EARTH_EARTH") (pintype "bidirectional"))
    )
    (net (code "94") (name "unconnected-(E1-LO+-Pad12)") (class "Default")
      (node (ref "E1") (pin "12") (pinfunction "LO+_12") (pintype "bidirectional"))
    )
    (net (code "95") (name "unconnected-(E1-LO--Pad11)") (class "Default")
      (node (ref "E1") (pin "11") (pinfunction "LO-_11") (pintype "bidirectional"))
    )
    (net (code "96") (name "unconnected-(E2-LO+-Pad12)") (class "Default")
      (node (ref "E2") (pin "12") (pinfunction "LO+_12") (pintype "bidirectional"))
    )
    (net (code "97") (name "unconnected-(E2-LO--Pad11)") (class "Default")
      (node (ref "E2") (pin "11") (pinfunction "LO-_11") (pintype "bidirectional"))
    )
    (net (code "98") (name "unconnected-(E3-LO+-Pad12)") (class "Default")
      (node (ref "E3") (pin "12") (pinfunction "LO+_12") (pintype "bidirectional"))
    )
    (net (code "99") (name "unconnected-(E3-LO--Pad11)") (class "Default")
      (node (ref "E3") (pin "11") (pinfunction "LO-_11") (pintype "bidirectional"))
    )
    (net (code "100") (name "unconnected-(E4-LO+-Pad12)") (class "Default")
      (node (ref "E4") (pin "12") (pinfunction "LO+_12") (pintype "bidirectional"))
    )
    (net (code "101") (name "unconnected-(E4-LO--Pad11)") (class "Default")
      (node (ref "E4") (pin "11") (pinfunction "LO-_11") (pintype "bidirectional"))
    )
  )
)
